# smb.net
KiCad netlist of a schematic drawn in EAGLE
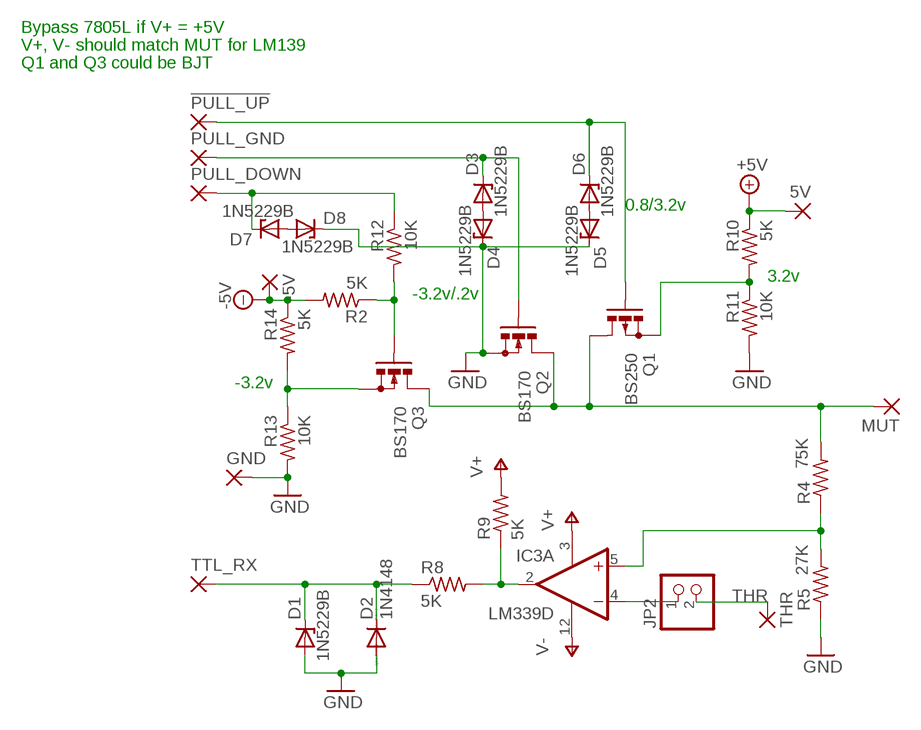
[diagram p0: schematic, sheet 1]

(export (version "E")
  (design (tool "Eeschema 10.0.6"))
  (components
    (comp (ref "!PULL_UP")
      (value "1,6/0,9")
      (footprint "eagle-import:1,6_0,9")
      (libsource (lib "eagle-import") (part "1,6/0,9"))
    )
    (comp (ref "-5V")
      (value "1,6/0,9")
      (footprint "eagle-import:1,6_0,9")
      (libsource (lib "eagle-import") (part "1,6/0,9"))
    )
    (comp (ref "5V")
      (value "1,6/0,9")
      (footprint "eagle-import:1,6_0,9")
      (libsource (lib "eagle-import") (part "1,6/0,9"))
    )
    (comp (ref "D1")
      (value "1N5229B")
      (footprint "eagle-import:SOD80C")
      (libsource (lib "eagle-import") (part "ZENER-DIODESOD80C"))
    )
    (comp (ref "D2")
      (value "1N4148")
      (footprint "eagle-import:SOD80C")
      (libsource (lib "eagle-import") (part "DIODE-SOD80C"))
    )
    (comp (ref "D3")
      (value "1N5229B")
      (footprint "eagle-import:SOD80C")
      (libsource (lib "eagle-import") (part "ZENER-DIODESOD80C"))
    )
    (comp (ref "D4")
      (value "1N5229B")
      (footprint "eagle-import:SOD80C")
      (libsource (lib "eagle-import") (part "ZENER-DIODESOD80C"))
    )
    (comp (ref "D5")
      (value "1N5229B")
      (footprint "eagle-import:SOD80C")
      (libsource (lib "eagle-import") (part "ZENER-DIODESOD80C"))
    )
    (comp (ref "D6")
      (value "1N5229B")
      (footprint "eagle-import:SOD80C")
      (libsource (lib "eagle-import") (part "ZENER-DIODESOD80C"))
    )
    (comp (ref "D7")
      (value "1N5229B")
      (footprint "eagle-import:SOD80C")
      (libsource (lib "eagle-import") (part "ZENER-DIODESOD80C"))
    )
    (comp (ref "D8")
      (value "1N5229B")
      (footprint "eagle-import:SOD80C")
      (libsource (lib "eagle-import") (part "ZENER-DIODESOD80C"))
    )
    (comp (ref "GND")
      (value "1,6/0,9")
      (footprint "eagle-import:1,6_0,9")
      (libsource (lib "eagle-import") (part "1,6/0,9"))
    )
    (comp (ref "IC3")
      (value "LM339D")
      (footprint "eagle-import:SO14")
      (libsource (lib "eagle-import") (part "LM339D"))
    )
    (comp (ref "JP2")
      (value "PINHD-1X2")
      (footprint "eagle-import:1X02")
      (libsource (lib "eagle-import") (part "PINHD-1X2"))
    )
    (comp (ref "MUT")
      (value "1,6/0,9")
      (footprint "eagle-import:1,6_0,9")
      (libsource (lib "eagle-import") (part "1,6/0,9"))
    )
    (comp (ref "PULL_DOWN")
      (value "1,6/0,9")
      (footprint "eagle-import:1,6_0,9")
      (libsource (lib "eagle-import") (part "1,6/0,9"))
    )
    (comp (ref "PULL_GND")
      (value "1,6/0,9")
      (footprint "eagle-import:1,6_0,9")
      (libsource (lib "eagle-import") (part "1,6/0,9"))
    )
    (comp (ref "Q1")
      (value "BS250")
      (footprint "eagle-import:SOT54E")
      (libsource (lib "eagle-import") (part "BS250"))
    )
    (comp (ref "Q2")
      (value "BS170")
      (footprint "eagle-import:SOT54E")
      (libsource (lib "eagle-import") (part "BS170"))
    )
    (comp (ref "Q3")
      (value "BS170")
      (footprint "eagle-import:SOT54E")
      (libsource (lib "eagle-import") (part "BS170"))
    )
    (comp (ref "R2")
      (value "5K")
      (footprint "eagle-import:M1206")
      (libsource (lib "eagle-import") (part "R-US_M1206"))
    )
    (comp (ref "R4")
      (value "75K")
      (footprint "eagle-import:M1206")
      (libsource (lib "eagle-import") (part "R-US_M1206"))
    )
    (comp (ref "R5")
      (value "27K")
      (footprint "eagle-import:M1206")
      (libsource (lib "eagle-import") (part "R-US_M1206"))
    )
    (comp (ref "R8")
      (value "5K")
      (footprint "eagle-import:M1206")
      (libsource (lib "eagle-import") (part "R-US_M1206"))
    )
    (comp (ref "R9")
      (value "5K")
      (footprint "eagle-import:M1206")
      (libsource (lib "eagle-import") (part "R-US_M1206"))
    )
    (comp (ref "R10")
      (value "5K")
      (footprint "eagle-import:M1206")
      (libsource (lib "eagle-import") (part "R-US_M1206"))
    )
    (comp (ref "R11")
      (value "10K")
      (footprint "eagle-import:M1206")
      (libsource (lib "eagle-import") (part "R-US_M1206"))
    )
    (comp (ref "R12")
      (value "10K")
      (footprint "eagle-import:M1206")
      (libsource (lib "eagle-import") (part "R-US_M1206"))
    )
    (comp (ref "R13")
      (value "10K")
      (footprint "eagle-import:M1206")
      (libsource (lib "eagle-import") (part "R-US_M1206"))
    )
    (comp (ref "R14")
      (value "5K")
      (footprint "eagle-import:M1206")
      (libsource (lib "eagle-import") (part "R-US_M1206"))
    )
    (comp (ref "THR")
      (value "1,6/0,9")
      (footprint "eagle-import:1,6_0,9")
      (libsource (lib "eagle-import") (part "1,6/0,9"))
    )
    (comp (ref "TTL_RX")
      (value "1,6/0,9")
      (footprint "eagle-import:1,6_0,9")
      (libsource (lib "eagle-import") (part "1,6/0,9"))
    )
  )
  (nets
    (net (code "1") (name "+5V") (class "Default")
      (node (ref "5V") (pin "1") (pinfunction "P_1") (pintype "passive"))
      (node (ref "R10") (pin "1") (pinfunction "1_1") (pintype "passive"))
    )
    (net (code "2") (name "-5V") (class "Default")
      (node (ref "-5V") (pin "1") (pinfunction "P_1") (pintype "passive"))
      (node (ref "R14") (pin "1") (pinfunction "1_1") (pintype "passive"))
      (node (ref "R2") (pin "2") (pinfunction "2_2") (pintype "passive"))
    )
    (net (code "3") (name "/THR") (class "Default")
      (node (ref "JP2") (pin "2") (pinfunction "2_2") (pintype "passive"))
      (node (ref "THR") (pin "1") (pinfunction "P_1") (pintype "passive"))
    )
    (net (code "4") (name "GND") (class "Default")
      (node (ref "D1") (pin "A") (pinfunction "A_A") (pintype "passive"))
      (node (ref "D2") (pin "A") (pinfunction "A_A") (pintype "passive"))
      (node (ref "D4") (pin "C") (pinfunction "C_C") (pintype "passive"))
      (node (ref "D5") (pin "C") (pinfunction "C_C") (pintype "passive"))
      (node (ref "D8") (pin "C") (pinfunction "C_C") (pintype "passive"))
      (node (ref "GND") (pin "1") (pinfunction "P_1") (pintype "passive"))
      (node (ref "Q2") (pin "S") (pinfunction "S_S") (pintype "passive"))
      (node (ref "R11") (pin "2") (pinfunction "2_2") (pintype "passive"))
      (node (ref "R13") (pin "2") (pinfunction "2_2") (pintype "passive"))
      (node (ref "R5") (pin "1") (pinfunction "1_1") (pintype "passive"))
    )
    (net (code "5") (name "Net-(!PULL_UP-P)") (class "Default")
      (node (ref "!PULL_UP") (pin "1") (pinfunction "P_1") (pintype "passive"))
      (node (ref "D6") (pin "C") (pinfunction "C_C") (pintype "passive"))
      (node (ref "Q1") (pin "G") (pinfunction "G_G") (pintype "passive"))
    )
    (net (code "6") (name "Net-(D3-PadA)") (class "Default")
      (node (ref "D3") (pin "A") (pinfunction "A_A") (pintype "passive"))
      (node (ref "D4") (pin "A") (pinfunction "A_A") (pintype "passive"))
    )
    (net (code "7") (name "Net-(D5-PadA)") (class "Default")
      (node (ref "D5") (pin "A") (pinfunction "A_A") (pintype "passive"))
      (node (ref "D6") (pin "A") (pinfunction "A_A") (pintype "passive"))
    )
    (net (code "8") (name "Net-(D7-PadA)") (class "Default")
      (node (ref "D7") (pin "A") (pinfunction "A_A") (pintype "passive"))
      (node (ref "D8") (pin "A") (pinfunction "A_A") (pintype "passive"))
    )
    (net (code "9") (name "Net-(IC3A-+IN)") (class "Default")
      (node (ref "IC3") (pin "5") (pinfunction "+IN_5") (pintype "input"))
      (node (ref "R4") (pin "1") (pinfunction "1_1") (pintype "passive"))
      (node (ref "R5") (pin "2") (pinfunction "2_2") (pintype "passive"))
    )
    (net (code "10") (name "Net-(IC3A--IN)") (class "Default")
      (node (ref "IC3") (pin "4") (pinfunction "-IN_4") (pintype "input"))
      (node (ref "JP2") (pin "1") (pinfunction "1_1") (pintype "passive"))
    )
    (net (code "11") (name "Net-(IC3A-OUT)") (class "Default")
      (node (ref "IC3") (pin "2") (pinfunction "OUT_2") (pintype "open_collector"))
      (node (ref "R8") (pin "2") (pinfunction "2_2") (pintype "passive"))
      (node (ref "R9") (pin "1") (pinfunction "1_1") (pintype "passive"))
    )
    (net (code "12") (name "Net-(MUT-P)") (class "Default")
      (node (ref "MUT") (pin "1") (pinfunction "P_1") (pintype "passive"))
      (node (ref "Q1") (pin "D") (pinfunction "D_D") (pintype "passive"))
      (node (ref "Q2") (pin "D") (pinfunction "D_D") (pintype "passive"))
      (node (ref "Q3") (pin "D") (pinfunction "D_D") (pintype "passive"))
      (node (ref "R4") (pin "2") (pinfunction "2_2") (pintype "passive"))
    )
    (net (code "13") (name "Net-(PULL_DOWN-P)") (class "Default")
      (node (ref "D7") (pin "C") (pinfunction "C_C") (pintype "passive"))
      (node (ref "PULL_DOWN") (pin "1") (pinfunction "P_1") (pintype "passive"))
      (node (ref "R12") (pin "1") (pinfunction "1_1") (pintype "passive"))
    )
    (net (code "14") (name "Net-(PULL_GND-P)") (class "Default")
      (node (ref "D3") (pin "C") (pinfunction "C_C") (pintype "passive"))
      (node (ref "PULL_GND") (pin "1") (pinfunction "P_1") (pintype "passive"))
      (node (ref "Q2") (pin "G") (pinfunction "G_G") (pintype "passive"))
    )
    (net (code "15") (name "Net-(Q1-PadS)") (class "Default")
      (node (ref "Q1") (pin "S") (pinfunction "S_S") (pintype "passive"))
      (node (ref "R10") (pin "2") (pinfunction "2_2") (pintype "passive"))
      (node (ref "R11") (pin "1") (pinfunction "1_1") (pintype "passive"))
    )
    (net (code "16") (name "Net-(Q3-PadG)") (class "Default")
      (node (ref "Q3") (pin "G") (pinfunction "G_G") (pintype "passive"))
      (node (ref "R12") (pin "2") (pinfunction "2_2") (pintype "passive"))
      (node (ref "R2") (pin "1") (pinfunction "1_1") (pintype "passive"))
    )
    (net (code "17") (name "Net-(Q3-PadS)") (class "Default")
      (node (ref "Q3") (pin "S") (pinfunction "S_S") (pintype "passive"))
      (node (ref "R13") (pin "1") (pinfunction "1_1") (pintype "passive"))
      (node (ref "R14") (pin "2") (pinfunction "2_2") (pintype "passive"))
    )
    (net (code "18") (name "Net-(TTL_RX-P)") (class "Default")
      (node (ref "D1") (pin "C") (pinfunction "C_C") (pintype "passive"))
      (node (ref "D2") (pin "C") (pinfunction "C_C") (pintype "passive"))
      (node (ref "R8") (pin "1") (pinfunction "1_1") (pintype "passive"))
      (node (ref "TTL_RX") (pin "1") (pinfunction "P_1") (pintype "passive"))
    )
    (net (code "19") (name "V+") (class "Default")
      (node (ref "IC3") (pin "3") (pinfunction "V+_3") (pintype "power_in"))
      (node (ref "R9") (pin "2") (pinfunction "2_2") (pintype "passive"))
    )
    (net (code "20") (name "V-") (class "Default")
      (node (ref "IC3") (pin "12") (pinfunction "GND_12") (pintype "power_in"))
    )
  )
)
